# USB.net
KiCad netlist of a schematic drawn in Altium Designer
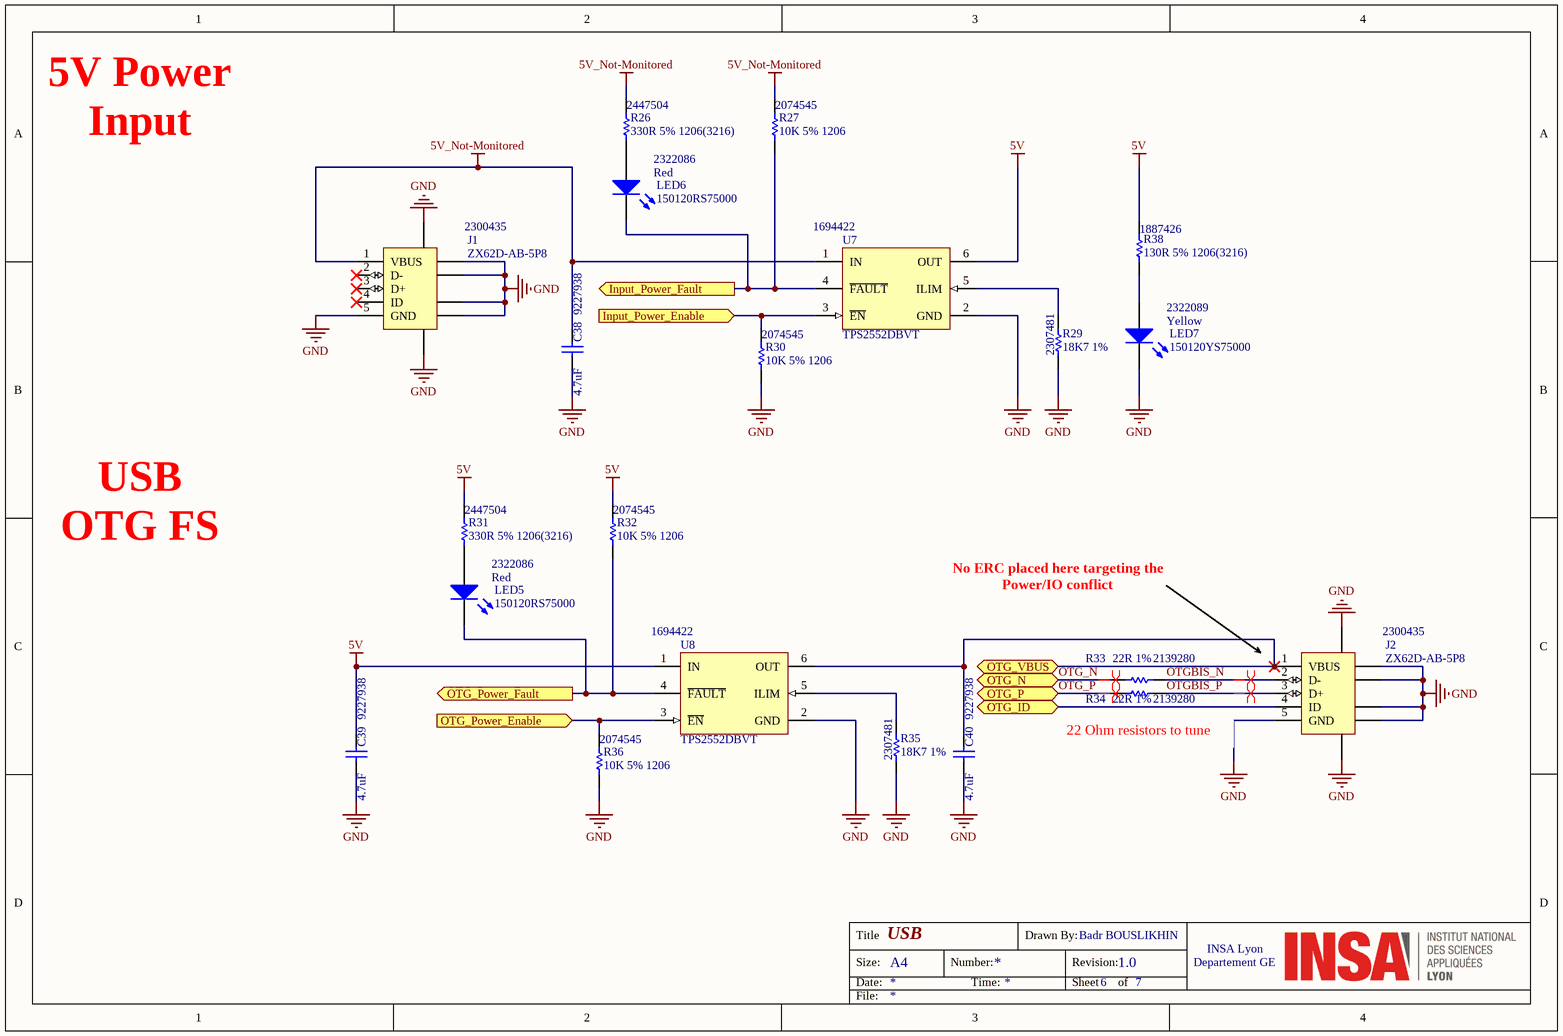
[diagram p0: USB.SchDoc]

(export (version "E")
  (design (tool "Eeschema 10.0.6"))
  (components
    (comp (ref "C38")
      (value "4.7uF")
      (footprint "CAPC1206(3216)190_N")
      (description "CAP 4.7uF 50V ±10% 1206 (3216 Metric) Thickness 1.9mm SMD")
      (fields (field (name "TOLERANCE") "±10%") (field (name "SUPPLIER PART NUMBER 1") "9227938"))
      (libsource (lib "Altium Content Vault") (part "CAP"))
    )
    (comp (ref "C39")
      (value "4.7uF")
      (footprint "CAPC1206(3216)190_N")
      (description "CAP 4.7uF 50V ±10% 1206 (3216 Metric) Thickness 1.9mm SMD")
      (fields (field (name "TOLERANCE") "±10%") (field (name "SUPPLIER PART NUMBER 1") "9227938"))
      (libsource (lib "Altium Content Vault") (part "CAP"))
    )
    (comp (ref "C40")
      (value "4.7uF")
      (footprint "CAPC1206(3216)190_N")
      (description "CAP 4.7uF 50V ±10% 1206 (3216 Metric) Thickness 1.9mm SMD")
      (fields (field (name "TOLERANCE") "±10%") (field (name "SUPPLIER PART NUMBER 1") "9227938"))
      (libsource (lib "Altium Content Vault") (part "CAP"))
    )
    (comp (ref "J1")
      (value "ZX62D-AB-5P8")
      (footprint "HIRO-ZX62D-AB-5P8_V")
      (fields
        (field (name "MANUFACTURER") "Hirose Electric")
        (field (name "SUPPLIER PART NUMBER 1") "2300435")
      )
      (libsource (lib "Altium Content Vault") (part "CMP-1349-00001-1"))
    )
    (comp (ref "J2")
      (value "ZX62D-AB-5P8")
      (footprint "HIRO-ZX62D-AB-5P8_V")
      (fields
        (field (name "MANUFACTURER") "Hirose Electric")
        (field (name "SUPPLIER PART NUMBER 1") "2300435")
      )
      (libsource (lib "Altium Content Vault") (part "CMP-1349-00001-1"))
    )
    (comp (ref "LED5")
      (value "150120RS75000")
      (footprint "1206_A")
      (description "SMD mono-color Chip LED, WL-SMCW, Red")
      (fields
        (field (name "COLOR") "Red")
        (field (name "MANUFACTURER") "Wuerth Elektronik")
        (field (name "SUPPLIER PART NUMBER 1") "2322086")
      )
      (libsource (lib "Altium Content Vault") (part "CMP-1426-00013-1"))
    )
    (comp (ref "LED6")
      (value "150120RS75000")
      (footprint "1206_A")
      (description "SMD mono-color Chip LED, WL-SMCW, Red")
      (fields
        (field (name "COLOR") "Red")
        (field (name "MANUFACTURER") "Wuerth Elektronik")
        (field (name "SUPPLIER PART NUMBER 1") "2322086")
      )
      (libsource (lib "Altium Content Vault") (part "CMP-1426-00013-1"))
    )
    (comp (ref "LED7")
      (value "150120YS75000")
      (footprint "1206_A")
      (description "SMD mono-color Chip LED, WL-SMCW, Yellow")
      (fields
        (field (name "MANUFACTURER") "Wuerth Elektronik")
        (field (name "COLOR") "Yellow")
        (field (name "SUPPLIER PART NUMBER 1") "2322089")
      )
      (libsource (lib "Altium Content Vault") (part "CMP-1426-00019-1"))
    )
    (comp (ref "R26")
      (value "330R 5% 1206(3216)")
      (footprint "RESC1206(3216)_M")
      (description "330R 0.25W 5% 1206 (3216 Metric)  SMD")
      (fields
        (field (name "TOLERANCE") "5 %")
        (field (name "POWER") "0.25 W")
        (field (name "SUPPLIER PART NUMBER 1") "2447504")
      )
      (libsource (lib "Altium Content Vault") (part "RES"))
    )
    (comp (ref "R27")
      (value "10K 5% 1206")
      (footprint "RESC1206(3216)_M")
      (description "10K 0.25W 5% 1206 (3216 Metric)  SMD")
      (fields
        (field (name "POWER") "0.25 W")
        (field (name "TOLERANCE") "5 %")
        (field (name "SUPPLIER PART NUMBER 1") "2074545")
      )
      (libsource (lib "Altium Content Vault") (part "CMP-1014-00098-1"))
    )
    (comp (ref "R29")
      (value "18K7 1%")
      (footprint "RESC1206(3216)_L")
      (description "18K7 0.25W 1% 1206 (3216 Metric)  SMD")
      (fields
        (field (name "POWER") "0.25 W")
        (field (name "TOLERANCE") "1 %")
        (field (name "SUPPLIER PART NUMBER 1") "2307481")
      )
      (libsource (lib "Altium Content Vault") (part "RES"))
    )
    (comp (ref "R30")
      (value "10K 5% 1206")
      (footprint "RESC1206(3216)_M")
      (description "10K 0.25W 5% 1206 (3216 Metric)  SMD")
      (fields
        (field (name "POWER") "0.25 W")
        (field (name "TOLERANCE") "5 %")
        (field (name "SUPPLIER PART NUMBER 1") "2074545")
      )
      (libsource (lib "Altium Content Vault") (part "CMP-1014-00098-1"))
    )
    (comp (ref "R31")
      (value "330R 5% 1206(3216)")
      (footprint "RESC1206(3216)_M")
      (description "330R 0.25W 5% 1206 (3216 Metric)  SMD")
      (fields
        (field (name "TOLERANCE") "5 %")
        (field (name "POWER") "0.25 W")
        (field (name "SUPPLIER PART NUMBER 1") "2447504")
      )
      (libsource (lib "Altium Content Vault") (part "RES"))
    )
    (comp (ref "R32")
      (value "10K 5% 1206")
      (footprint "RESC1206(3216)_M")
      (description "10K 0.25W 5% 1206 (3216 Metric)  SMD")
      (fields
        (field (name "POWER") "0.25 W")
        (field (name "TOLERANCE") "5 %")
        (field (name "SUPPLIER PART NUMBER 1") "2074545")
      )
      (libsource (lib "Altium Content Vault") (part "CMP-1014-00098-1"))
    )
    (comp (ref "R33")
      (value "22R 1%")
      (footprint "RESC0603(1608)_M")
      (description "22R 0.1W 1% 0603 (1608 Metric)  SMD")
      (fields
        (field (name "POWER") "0.1 W")
        (field (name "TOLERANCE") "1 %")
        (field (name "SUPPLIER PART NUMBER 1") "2139280")
      )
      (libsource (lib "Altium Content Vault") (part "RES"))
    )
    (comp (ref "R34")
      (value "22R 1%")
      (footprint "RESC0603(1608)_M")
      (description "22R 0.1W 1% 0603 (1608 Metric)  SMD")
      (fields
        (field (name "POWER") "0.1 W")
        (field (name "TOLERANCE") "1 %")
        (field (name "SUPPLIER PART NUMBER 1") "2139280")
      )
      (libsource (lib "Altium Content Vault") (part "RES"))
    )
    (comp (ref "R35")
      (value "18K7 1%")
      (footprint "RESC1206(3216)_L")
      (description "18K7 0.25W 1% 1206 (3216 Metric)  SMD")
      (fields
        (field (name "POWER") "0.25 W")
        (field (name "TOLERANCE") "1 %")
        (field (name "SUPPLIER PART NUMBER 1") "2307481")
      )
      (libsource (lib "Altium Content Vault") (part "RES"))
    )
    (comp (ref "R36")
      (value "10K 5% 1206")
      (footprint "RESC1206(3216)_M")
      (description "10K 0.25W 5% 1206 (3216 Metric)  SMD")
      (fields
        (field (name "POWER") "0.25 W")
        (field (name "TOLERANCE") "5 %")
        (field (name "SUPPLIER PART NUMBER 1") "2074545")
      )
      (libsource (lib "Altium Content Vault") (part "CMP-1014-00098-1"))
    )
    (comp (ref "R38")
      (value "130R 5% 1206(3216)")
      (footprint "RESC1206(3216)_L")
      (description "130R 0.25W 5% 1206 (3216 Metric)  SMD")
      (fields
        (field (name "TOLERANCE") "5 %")
        (field (name "POWER") "0.25 W")
        (field (name "SUPPLIER PART NUMBER 1") "1887426")
      )
      (libsource (lib "Altium Content Vault") (part "RES"))
    )
    (comp (ref "U7")
      (value "TPS2552DBVT")
      (footprint "DBV6_L")
      (fields
        (field (name "MANUFACTURER") "Texas Instruments")
        (field (name "SUPPLIER PART NUMBER 1") "1694422")
      )
      (libsource (lib "Altium Content Vault") (part "TI-TPS2552DBV6"))
    )
    (comp (ref "U8")
      (value "TPS2552DBVT")
      (footprint "DBV6_L")
      (fields
        (field (name "MANUFACTURER") "Texas Instruments")
        (field (name "SUPPLIER PART NUMBER 1") "1694422")
      )
      (libsource (lib "Altium Content Vault") (part "TI-TPS2552DBV6"))
    )
  )
  (nets
    (net (code "1") (name "/Input_Power_Enable") (class "Default")
      (node (ref "R30") (pin "2") (pinfunction "2_2") (pintype "passive"))
      (node (ref "U7") (pin "3") (pinfunction "~{EN}_3") (pintype "input"))
    )
    (net (code "2") (name "/Input_Power_Fault") (class "Default")
      (node (ref "LED6") (pin "1") (pinfunction "K_1") (pintype "passive"))
      (node (ref "R27") (pin "1") (pinfunction "1_1") (pintype "passive"))
      (node (ref "U7") (pin "4") (pinfunction "~{FAULT}_4") (pintype "tri_state"))
    )
    (net (code "3") (name "/OTGBIS_N") (class "Default")
      (node (ref "J2") (pin "2") (pinfunction "D-_2") (pintype "bidirectional"))
      (node (ref "R33") (pin "2") (pinfunction "2_2") (pintype "passive"))
    )
    (net (code "4") (name "/OTGBIS_P") (class "Default")
      (node (ref "J2") (pin "3") (pinfunction "D+_3") (pintype "bidirectional"))
      (node (ref "R34") (pin "2") (pinfunction "2_2") (pintype "passive"))
    )
    (net (code "5") (name "/OTG_ID") (class "Default")
      (node (ref "J2") (pin "4") (pinfunction "ID_4") (pintype "passive"))
    )
    (net (code "6") (name "/OTG_N") (class "Default")
      (node (ref "R33") (pin "1") (pinfunction "1_1") (pintype "passive"))
    )
    (net (code "7") (name "/OTG_P") (class "Default")
      (node (ref "R34") (pin "1") (pinfunction "1_1") (pintype "passive"))
    )
    (net (code "8") (name "/OTG_Power_Enable") (class "Default")
      (node (ref "R36") (pin "2") (pinfunction "2_2") (pintype "passive"))
      (node (ref "U8") (pin "3") (pinfunction "~{EN}_3") (pintype "input"))
    )
    (net (code "9") (name "/OTG_Power_Fault") (class "Default")
      (node (ref "LED5") (pin "1") (pinfunction "K_1") (pintype "passive"))
      (node (ref "R32") (pin "1") (pinfunction "1_1") (pintype "passive"))
      (node (ref "U8") (pin "4") (pinfunction "~{FAULT}_4") (pintype "tri_state"))
    )
    (net (code "10") (name "/OTG_VBUS") (class "Default")
      (node (ref "C40") (pin "2") (pinfunction "2_2") (pintype "passive"))
      (node (ref "J2") (pin "1") (pinfunction "VBUS_1") (pintype "power_in"))
      (node (ref "U8") (pin "6") (pinfunction "OUT_6") (pintype "power_in"))
    )
    (net (code "11") (name "5V") (class "Default")
      (node (ref "C39") (pin "2") (pinfunction "2_2") (pintype "passive"))
      (node (ref "R31") (pin "2") (pinfunction "2_2") (pintype "passive"))
      (node (ref "R32") (pin "2") (pinfunction "2_2") (pintype "passive"))
      (node (ref "R38") (pin "2") (pinfunction "2_2") (pintype "passive"))
      (node (ref "U7") (pin "6") (pinfunction "OUT_6") (pintype "power_in"))
      (node (ref "U8") (pin "1") (pinfunction "IN_1") (pintype "power_in"))
    )
    (net (code "12") (name "5V_Not-Monitored") (class "Default")
      (node (ref "C38") (pin "2") (pinfunction "2_2") (pintype "passive"))
      (node (ref "J1") (pin "1") (pinfunction "VBUS_1") (pintype "power_in"))
      (node (ref "R26") (pin "2") (pinfunction "2_2") (pintype "passive"))
      (node (ref "R27") (pin "2") (pinfunction "2_2") (pintype "passive"))
      (node (ref "U7") (pin "1") (pinfunction "IN_1") (pintype "power_in"))
    )
    (net (code "13") (name "GND") (class "Default")
      (node (ref "C38") (pin "1") (pinfunction "1_1") (pintype "passive"))
      (node (ref "C39") (pin "1") (pinfunction "1_1") (pintype "passive"))
      (node (ref "C40") (pin "1") (pinfunction "1_1") (pintype "passive"))
      (node (ref "J1") (pin "10") (pinfunction "SHLD_10") (pintype "passive"))
      (node (ref "J1") (pin "11") (pinfunction "SHLD_11") (pintype "passive"))
      (node (ref "J1") (pin "5") (pinfunction "GND_5") (pintype "power_in"))
      (node (ref "J1") (pin "6") (pinfunction "SHLD_6") (pintype "passive"))
      (node (ref "J1") (pin "7") (pinfunction "SHLD_7") (pintype "passive"))
      (node (ref "J1") (pin "8") (pinfunction "SHLD_8") (pintype "passive"))
      (node (ref "J1") (pin "9") (pinfunction "SHLD_9") (pintype "passive"))
      (node (ref "J2") (pin "10") (pinfunction "SHLD_10") (pintype "passive"))
      (node (ref "J2") (pin "11") (pinfunction "SHLD_11") (pintype "passive"))
      (node (ref "J2") (pin "5") (pinfunction "GND_5") (pintype "power_in"))
      (node (ref "J2") (pin "6") (pinfunction "SHLD_6") (pintype "passive"))
      (node (ref "J2") (pin "7") (pinfunction "SHLD_7") (pintype "passive"))
      (node (ref "J2") (pin "8") (pinfunction "SHLD_8") (pintype "passive"))
      (node (ref "J2") (pin "9") (pinfunction "SHLD_9") (pintype "passive"))
      (node (ref "LED7") (pin "1") (pinfunction "K_1") (pintype "passive"))
      (node (ref "R29") (pin "1") (pinfunction "1_1") (pintype "passive"))
      (node (ref "R30") (pin "1") (pinfunction "1_1") (pintype "passive"))
      (node (ref "R35") (pin "1") (pinfunction "1_1") (pintype "passive"))
      (node (ref "R36") (pin "1") (pinfunction "1_1") (pintype "passive"))
      (node (ref "U7") (pin "2") (pinfunction "GND_2") (pintype "power_in"))
      (node (ref "U8") (pin "2") (pinfunction "GND_2") (pintype "power_in"))
    )
    (net (code "14") (name "Net-(LED5-A)") (class "Default")
      (node (ref "LED5") (pin "2") (pinfunction "A_2") (pintype "passive"))
      (node (ref "R31") (pin "1") (pinfunction "1_1") (pintype "passive"))
    )
    (net (code "15") (name "Net-(LED6-A)") (class "Default")
      (node (ref "LED6") (pin "2") (pinfunction "A_2") (pintype "passive"))
      (node (ref "R26") (pin "1") (pinfunction "1_1") (pintype "passive"))
    )
    (net (code "16") (name "Net-(LED7-A)") (class "Default")
      (node (ref "LED7") (pin "2") (pinfunction "A_2") (pintype "passive"))
      (node (ref "R38") (pin "1") (pinfunction "1_1") (pintype "passive"))
    )
    (net (code "17") (name "Net-(U7-ILIM)") (class "Default")
      (node (ref "R29") (pin "2") (pinfunction "2_2") (pintype "passive"))
      (node (ref "U7") (pin "5") (pinfunction "ILIM_5") (pintype "input"))
    )
    (net (code "18") (name "Net-(U8-ILIM)") (class "Default")
      (node (ref "R35") (pin "2") (pinfunction "2_2") (pintype "passive"))
      (node (ref "U8") (pin "5") (pinfunction "ILIM_5") (pintype "input"))
    )
    (net (code "19") (name "unconnected-(J1-D+-Pad3)") (class "Default")
      (node (ref "J1") (pin "3") (pinfunction "D+_3") (pintype "bidirectional+no_connect"))
    )
    (net (code "20") (name "unconnected-(J1-D--Pad2)") (class "Default")
      (node (ref "J1") (pin "2") (pinfunction "D-_2") (pintype "bidirectional+no_connect"))
    )
    (net (code "21") (name "unconnected-(J1-ID-Pad4)") (class "Default")
      (node (ref "J1") (pin "4") (pinfunction "ID_4") (pintype "passive+no_connect"))
    )
  )
)
